# humidityDetector.net
KiCad netlist of a schematic drawn in Altium Designer
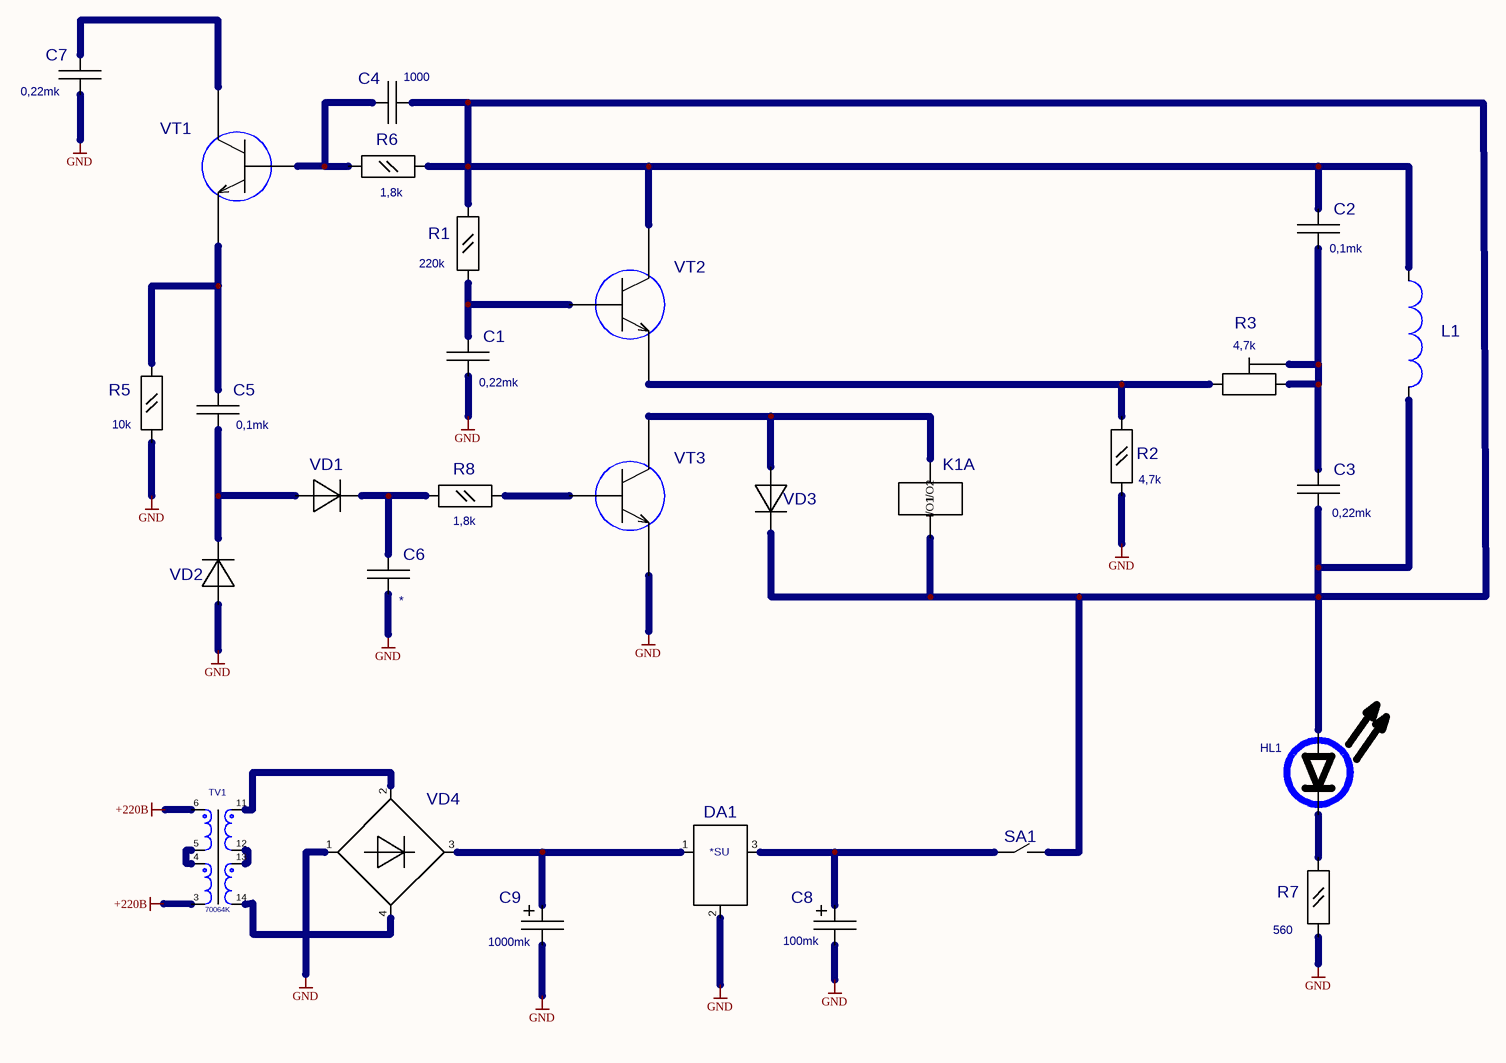
[diagram p0: humidityDetector.SchDoc]

(export (version "E")
  (design (tool "Eeschema 10.0.6"))
  (components
    (comp (ref "C1")
      (value "0,22mk")
      (footprint "CC2220")
      (description "CC2220")
      (libsource (lib "*") (part "CC2220"))
    )
    (comp (ref "C2")
      (value "0,1mk")
      (footprint "CC2220")
      (description "CC2220")
      (libsource (lib "*") (part "CC2220"))
    )
    (comp (ref "C3")
      (value "0,22mk")
      (footprint "CC2220")
      (description "CC2220")
      (libsource (lib "*") (part "CC2220"))
    )
    (comp (ref "C4")
      (value "1000")
      (footprint "CC2220")
      (description "CC2220")
      (libsource (lib "*") (part "CC2220"))
    )
    (comp (ref "C5")
      (value "0,1mk")
      (footprint "CC2220")
      (description "CC2220")
      (libsource (lib "*") (part "CC2220"))
    )
    (comp (ref "C6")
      (value "CC2220")
      (footprint "CC2220")
      (fields (field (name "ALTIUM_VALUE") "*"))
      (libsource (lib "*") (part "CC2220"))
    )
    (comp (ref "C7")
      (value "0,22mk")
      (footprint "CC2220")
      (description "CC2220")
      (libsource (lib "*") (part "CC2220"))
    )
    (comp (ref "C8")
      (value "100mk")
      (footprint "K534A-1")
      (description "K534A-1")
      (libsource (lib "*") (part "K534A-1"))
    )
    (comp (ref "C9")
      (value "1000mk")
      (footprint "K534A-1")
      (description "K534A-1")
      (libsource (lib "*") (part "K534A-1"))
    )
    (comp (ref "DA1") (value "КР1158ЕН5") (footprint "KT26-3") (libsource (lib "*") (part "КР1158ЕН5")))
    (comp (ref "HL1") (value "АЛЗ07Б") (footprint "АЛЗ07Б") (libsource (lib "*") (part "АЛЗ07Б")))
    (comp (ref "K1") (value "РЭК53") (footprint "REK53") (libsource (lib "*") (part "РЭК53")))
    (comp (ref "L1")
      (value "1812CS-472XJL")
      (footprint "1812CS")
      (description "Inductor")
      (libsource (lib "*") (part "1812CS-472XJL"))
    )
    (comp (ref "R1")
      (value "220k")
      (footprint "C2-33H-0.125W")
      (description "C2-33H-0.125W_OLD_UGO")
      (fields (field (name "AUTOR") "pcbdesigner.ru"))
      (libsource (lib "*") (part "C2-33H-0.125W_OLD_UGO"))
    )
    (comp (ref "R2")
      (value "4,7k")
      (footprint "C2-33H-0.125W")
      (description "C2-33H-0.125W_OLD_UGO")
      (fields (field (name "AUTOR") "pcbdesigner.ru"))
      (libsource (lib "*") (part "C2-33H-0.125W_OLD_UGO"))
    )
    (comp (ref "R3")
      (value "4,7k")
      (footprint "16K1")
      (description "16K1")
      (libsource (lib "*") (part "16K1"))
    )
    (comp (ref "R5")
      (value "10k")
      (footprint "C2-33H-0.125W")
      (description "C2-33H-0.125W_OLD_UGO")
      (fields (field (name "AUTOR") "pcbdesigner.ru"))
      (libsource (lib "*") (part "C2-33H-0.125W_OLD_UGO"))
    )
    (comp (ref "R6")
      (value "1,8k")
      (footprint "C2-33H-0.125W")
      (description "C2-33H-0.125W_OLD_UGO")
      (fields (field (name "AUTOR") "pcbdesigner.ru"))
      (libsource (lib "*") (part "C2-33H-0.125W_OLD_UGO"))
    )
    (comp (ref "R7")
      (value "560")
      (footprint "C2-33H-0.125W")
      (description "C2-33H-0.125W_OLD_UGO")
      (fields (field (name "AUTOR") "pcbdesigner.ru"))
      (libsource (lib "*") (part "C2-33H-0.125W_OLD_UGO"))
    )
    (comp (ref "R8")
      (value "1,8k")
      (footprint "C2-33H-0.125W")
      (description "C2-33H-0.125W_OLD_UGO")
      (fields (field (name "AUTOR") "pcbdesigner.ru"))
      (libsource (lib "*") (part "C2-33H-0.125W_OLD_UGO"))
    )
    (comp (ref "SA1")
      (value "8AS9M2RE")
      (footprint "8AS9M2RE")
      (fields (field (name "AUTHOR") "pcbdesigner.ru"))
      (libsource (lib "*") (part "8AS9M2RE"))
    )
    (comp (ref "TV1") (value "70064K") (footprint "70000_72400_SERIES") (libsource (lib "*") (part "70064K")))
    (comp (ref "VD1") (value "KD522") (footprint "VDD10") (libsource (lib "*") (part "KD522")))
    (comp (ref "VD2") (value "KD522") (footprint "VDD10") (libsource (lib "*") (part "KD522")))
    (comp (ref "VD3") (value "KD522") (footprint "VDD10") (libsource (lib "*") (part "KD522")))
    (comp (ref "VD4") (value "KC412") (footprint "KC412") (libsource (lib "*") (part "KC412")))
    (comp (ref "VT1") (value "КТ312") (footprint "КТ312") (libsource (lib "") (part "КТ312_1")))
    (comp (ref "VT2") (value "КТ312") (footprint "КТ312") (libsource (lib "*") (part "КТ312")))
    (comp (ref "VT3") (value "КТ312") (footprint "КТ312") (libsource (lib "*") (part "КТ312")))
  )
  (nets
    (net (code "1") (name "+220B") (class "Default")
      (node (ref "TV1") (pin "3") (pinfunction "3_3") (pintype "passive"))
      (node (ref "TV1") (pin "6") (pinfunction "6_6") (pintype "passive"))
    )
    (net (code "2") (name "GND") (class "Default")
      (node (ref "C1") (pin "2") (pinfunction "2_2") (pintype "passive"))
      (node (ref "C6") (pin "2") (pinfunction "2_2") (pintype "passive"))
      (node (ref "C7") (pin "2") (pinfunction "2_2") (pintype "passive"))
      (node (ref "C8") (pin "2") (pinfunction "I/OB_2") (pintype "passive"))
      (node (ref "C9") (pin "2") (pinfunction "I/OB_2") (pintype "passive"))
      (node (ref "DA1") (pin "2") (pinfunction "GND0_2") (pintype "passive"))
      (node (ref "R2") (pin "1") (pinfunction "1_1") (pintype "passive"))
      (node (ref "R5") (pin "2") (pinfunction "2_2") (pintype "passive"))
      (node (ref "R7") (pin "2") (pinfunction "2_2") (pintype "passive"))
      (node (ref "VD2") (pin "2") (pinfunction "I/O2_2") (pintype "passive"))
      (node (ref "VD4") (pin "1") (pinfunction "I/O1_1") (pintype "passive"))
      (node (ref "VT3") (pin "E") (pinfunction "E_E") (pintype "passive"))
    )
    (net (code "3") (name "Net-(C1-Pad1)") (class "Default")
      (node (ref "C1") (pin "1") (pinfunction "1_1") (pintype "passive"))
      (node (ref "R1") (pin "2") (pinfunction "2_2") (pintype "passive"))
      (node (ref "VT2") (pin "B") (pinfunction "B_B") (pintype "passive"))
    )
    (net (code "4") (name "Net-(C2-Pad2)") (class "Default")
      (node (ref "C2") (pin "2") (pinfunction "2_2") (pintype "passive"))
      (node (ref "C3") (pin "1") (pinfunction "1_1") (pintype "passive"))
      (node (ref "R3") (pin "2") (pinfunction "2_2") (pintype "passive"))
      (node (ref "R3") (pin "3") (pinfunction "3_3") (pintype "passive"))
    )
    (net (code "5") (name "Net-(C4-Pad1)") (class "Default")
      (node (ref "C4") (pin "1") (pinfunction "1_1") (pintype "passive"))
      (node (ref "R6") (pin "2") (pinfunction "2_2") (pintype "passive"))
      (node (ref "VT1") (pin "B") (pinfunction "B_B") (pintype "passive"))
    )
    (net (code "6") (name "Net-(C5-Pad1)") (class "Default")
      (node (ref "C5") (pin "1") (pinfunction "1_1") (pintype "passive"))
      (node (ref "R5") (pin "1") (pinfunction "1_1") (pintype "passive"))
      (node (ref "VT1") (pin "E") (pinfunction "E_E") (pintype "passive"))
    )
    (net (code "7") (name "Net-(C7-Pad1)") (class "Default")
      (node (ref "C7") (pin "1") (pinfunction "1_1") (pintype "passive"))
      (node (ref "VT1") (pin "K") (pinfunction "K_K") (pintype "passive"))
    )
    (net (code "8") (name "Net-(C8-I{slash}OA)") (class "Default")
      (node (ref "C8") (pin "1") (pinfunction "I/OA_1") (pintype "passive"))
      (node (ref "DA1") (pin "3") (pinfunction "OUT0_3") (pintype "passive"))
      (node (ref "SA1") (pin "2") (pinfunction "2_2") (pintype "passive"))
    )
    (net (code "9") (name "Net-(C9-I{slash}OA)") (class "Default")
      (node (ref "C9") (pin "1") (pinfunction "I/OA_1") (pintype "passive"))
      (node (ref "DA1") (pin "1") (pinfunction "IN0_1") (pintype "passive"))
      (node (ref "VD4") (pin "3") (pinfunction "I/O3_3") (pintype "passive"))
    )
    (net (code "10") (name "Net-(HL1-0-Pad1)") (class "Default")
      (node (ref "HL1") (pin "1") (pinfunction "0_1") (pintype "passive"))
      (node (ref "R7") (pin "1") (pinfunction "1_1") (pintype "passive"))
    )
    (net (code "11") (name "Net-(K1-I{slash}O1)") (class "Default")
      (node (ref "C2") (pin "1") (pinfunction "1_1") (pintype "passive"))
      (node (ref "C3") (pin "2") (pinfunction "2_2") (pintype "passive"))
      (node (ref "C4") (pin "2") (pinfunction "2_2") (pintype "passive"))
      (node (ref "HL1") (pin "0") (pinfunction "0_0") (pintype "passive"))
      (node (ref "K1") (pin "1") (pinfunction "I/O1_1") (pintype "passive"))
      (node (ref "L1") (pin "1") (pinfunction "1_1") (pintype "passive"))
      (node (ref "L1") (pin "2") (pinfunction "2_2") (pintype "passive"))
      (node (ref "R1") (pin "1") (pinfunction "1_1") (pintype "passive"))
      (node (ref "R6") (pin "1") (pinfunction "1_1") (pintype "passive"))
      (node (ref "SA1") (pin "1") (pinfunction "1_1") (pintype "passive"))
      (node (ref "VD3") (pin "1") (pinfunction "I/O1_1") (pintype "passive"))
      (node (ref "VT2") (pin "K") (pinfunction "K_K") (pintype "passive"))
    )
    (net (code "12") (name "Net-(K1-I{slash}O2)") (class "Default")
      (node (ref "K1") (pin "2") (pinfunction "I/O2_2") (pintype "passive"))
      (node (ref "VD3") (pin "2") (pinfunction "I/O2_2") (pintype "passive"))
      (node (ref "VT3") (pin "K") (pinfunction "K_K") (pintype "passive"))
    )
    (net (code "13") (name "Net-(R2-Pad2)") (class "Default")
      (node (ref "R2") (pin "2") (pinfunction "2_2") (pintype "passive"))
      (node (ref "R3") (pin "1") (pinfunction "1_1") (pintype "passive"))
      (node (ref "VT2") (pin "E") (pinfunction "E_E") (pintype "passive"))
    )
    (net (code "14") (name "Net-(R8-Pad1)") (class "Default")
      (node (ref "R8") (pin "1") (pinfunction "1_1") (pintype "passive"))
      (node (ref "VT3") (pin "B") (pinfunction "B_B") (pintype "passive"))
    )
    (net (code "15") (name "Net-(TV1-Pad4)") (class "Default")
      (node (ref "TV1") (pin "4") (pinfunction "4_4") (pintype "passive"))
      (node (ref "TV1") (pin "5") (pinfunction "5_5") (pintype "passive"))
    )
    (net (code "16") (name "Net-(TV1-Pad12)") (class "Default")
      (node (ref "TV1") (pin "12") (pinfunction "12_12") (pintype "passive"))
      (node (ref "TV1") (pin "13") (pinfunction "13_13") (pintype "passive"))
    )
    (net (code "17") (name "Net-(VD1-I{slash}O1)") (class "Default")
      (node (ref "C6") (pin "1") (pinfunction "1_1") (pintype "passive"))
      (node (ref "R8") (pin "2") (pinfunction "2_2") (pintype "passive"))
      (node (ref "VD1") (pin "1") (pinfunction "I/O1_1") (pintype "passive"))
    )
    (net (code "18") (name "Net-(VD1-I{slash}O2)") (class "Default")
      (node (ref "C5") (pin "2") (pinfunction "2_2") (pintype "passive"))
      (node (ref "VD1") (pin "2") (pinfunction "I/O2_2") (pintype "passive"))
      (node (ref "VD2") (pin "1") (pinfunction "I/O1_1") (pintype "passive"))
    )
    (net (code "19") (name "Net-(VD4-I{slash}O2)") (class "Default")
      (node (ref "TV1") (pin "11") (pinfunction "11_11") (pintype "passive"))
      (node (ref "VD4") (pin "2") (pinfunction "I/O2_2") (pintype "passive"))
    )
    (net (code "20") (name "Net-(VD4-I{slash}O4)") (class "Default")
      (node (ref "TV1") (pin "14") (pinfunction "14_14") (pintype "passive"))
      (node (ref "VD4") (pin "4") (pinfunction "I/O4_4") (pintype "passive"))
    )
    (net (code "21") (name "unconnected-(TV1-Pad1)") (class "Default")
      (node (ref "TV1") (pin "1") (pintype "passive"))
    )
    (net (code "22") (name "unconnected-(TV1-Pad2)") (class "Default")
      (node (ref "TV1") (pin "2") (pintype "passive"))
    )
    (net (code "23") (name "unconnected-(TV1-Pad7)") (class "Default")
      (node (ref "TV1") (pin "7") (pintype "passive"))
    )
    (net (code "24") (name "unconnected-(TV1-Pad8)") (class "Default")
      (node (ref "TV1") (pin "8") (pintype "passive"))
    )
    (net (code "25") (name "unconnected-(TV1-Pad9)") (class "Default")
      (node (ref "TV1") (pin "9") (pintype "passive"))
    )
    (net (code "26") (name "unconnected-(TV1-Pad10)") (class "Default")
      (node (ref "TV1") (pin "10") (pintype "passive"))
    )
    (net (code "27") (name "unconnected-(TV1-Pad15)") (class "Default")
      (node (ref "TV1") (pin "15") (pintype "passive"))
    )
    (net (code "28") (name "unconnected-(TV1-Pad16)") (class "Default")
      (node (ref "TV1") (pin "16") (pintype "passive"))
    )
    (net (code "29") (name "unconnected-(TV1-Pad17)") (class "Default")
      (node (ref "TV1") (pin "17") (pintype "passive"))
    )
    (net (code "30") (name "unconnected-(TV1-Pad18)") (class "Default")
      (node (ref "TV1") (pin "18") (pintype "passive"))
    )
    (net (code "31") (name "unconnected-(TV1-Pad19)") (class "Default")
      (node (ref "TV1") (pin "19") (pintype "passive"))
    )
    (net (code "32") (name "unconnected-(TV1-Pad20)") (class "Default")
      (node (ref "TV1") (pin "20") (pintype "passive"))
    )
    (net (code "33") (name "unconnected-(TV1-Pad21)") (class "Default")
      (node (ref "TV1") (pin "21") (pintype "passive"))
    )
    (net (code "34") (name "unconnected-(TV1-Pad22)") (class "Default")
      (node (ref "TV1") (pin "22") (pintype "passive"))
    )
    (net (code "35") (name "unconnected-(TV1-Pad23)") (class "Default")
      (node (ref "TV1") (pin "23") (pintype "passive"))
    )
    (net (code "36") (name "unconnected-(TV1-Pad24)") (class "Default")
      (node (ref "TV1") (pin "24") (pintype "passive"))
    )
    (net (code "37") (name "unconnected-(TV1-Pad25)") (class "Default")
      (node (ref "TV1") (pin "25") (pintype "passive"))
    )
    (net (code "38") (name "unconnected-(TV1-Pad26)") (class "Default")
      (node (ref "TV1") (pin "26") (pintype "passive"))
    )
    (net (code "39") (name "unconnected-(TV1-Pad27)") (class "Default")
      (node (ref "TV1") (pin "27") (pintype "passive"))
    )
    (net (code "40") (name "unconnected-(TV1-Pad28)") (class "Default")
      (node (ref "TV1") (pin "28") (pintype "passive"))
    )
    (net (code "41") (name "unconnected-(TV1-Pad29)") (class "Default")
      (node (ref "TV1") (pin "29") (pintype "passive"))
    )
    (net (code "42") (name "unconnected-(TV1-Pad30)") (class "Default")
      (node (ref "TV1") (pin "30") (pintype "passive"))
    )
    (net (code "43") (name "unconnected-(TV1-Pad31)") (class "Default")
      (node (ref "TV1") (pin "31") (pintype "passive"))
    )
    (net (code "44") (name "unconnected-(TV1-Pad32)") (class "Default")
      (node (ref "TV1") (pin "32") (pintype "passive"))
    )
    (net (code "45") (name "unconnected-(TV1-Pad33)") (class "Default")
      (node (ref "TV1") (pin "33") (pintype "passive"))
    )
    (net (code "46") (name "unconnected-(TV1-Pad34)") (class "Default")
      (node (ref "TV1") (pin "34") (pintype "passive"))
    )
    (net (code "47") (name "unconnected-(TV1-Pad35)") (class "Default")
      (node (ref "TV1") (pin "35") (pintype "passive"))
    )
  )
)
